# Breakout.net
KiCad netlist of a schematic drawn in EAGLE
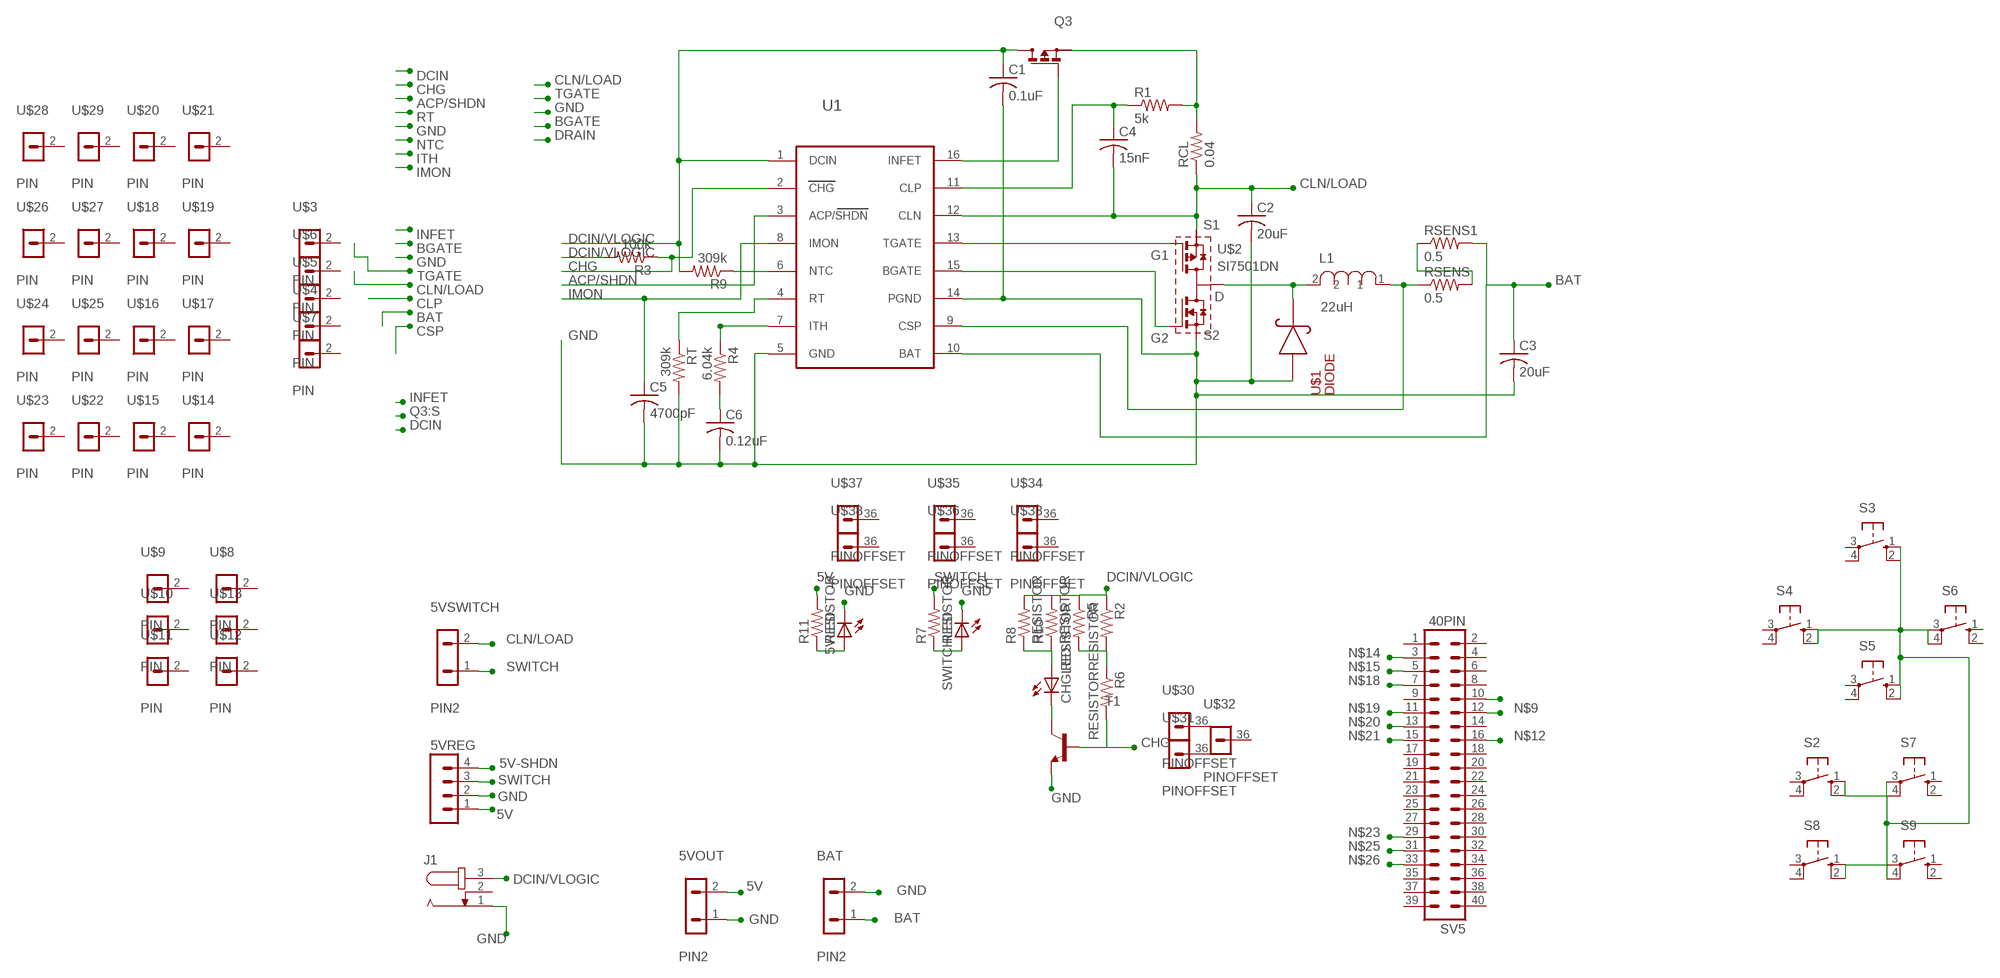
[diagram p0: schematic, sheet 1]

(export (version "E")
  (design (tool "Eeschema 10.0.6"))
  (components
    (comp (ref "5VLED")
      (value "LED5MM")
      (footprint "eagle-import:LED5MM")
      (libsource (lib "eagle-import") (part "LED5MM"))
    )
    (comp (ref "5VOUT")
      (value "PIN2")
      (footprint "eagle-import:PIN2")
      (libsource (lib "eagle-import") (part "PIN2"))
    )
    (comp (ref "5VREG")
      (value "MA04-1")
      (footprint "eagle-import:MA04-1")
      (libsource (lib "eagle-import") (part "MA04-1"))
    )
    (comp (ref "5VSWITCH")
      (value "PIN2")
      (footprint "eagle-import:PIN2")
      (libsource (lib "eagle-import") (part "PIN2"))
    )
    (comp (ref "BAT")
      (value "PIN2")
      (footprint "eagle-import:PIN2")
      (libsource (lib "eagle-import") (part "PIN2"))
    )
    (comp (ref "C1")
      (value "0.1uF")
      (footprint "eagle-import:C1210")
      (libsource (lib "eagle-import") (part "C-USC1210"))
    )
    (comp (ref "C2")
      (value "20uF")
      (footprint "eagle-import:C1210")
      (libsource (lib "eagle-import") (part "C-USC1210"))
    )
    (comp (ref "C3")
      (value "20uF")
      (footprint "eagle-import:C1210")
      (libsource (lib "eagle-import") (part "C-USC1210"))
    )
    (comp (ref "C4")
      (value "15nF")
      (footprint "eagle-import:C1210")
      (libsource (lib "eagle-import") (part "C-USC1210"))
    )
    (comp (ref "C5")
      (value "4700pF")
      (footprint "eagle-import:C1210")
      (libsource (lib "eagle-import") (part "C-USC1210"))
    )
    (comp (ref "C6")
      (value "0.12uF")
      (footprint "eagle-import:C1210")
      (libsource (lib "eagle-import") (part "C-USC1210"))
    )
    (comp (ref "CHGLED")
      (value "LED5MM")
      (footprint "eagle-import:LED5MM")
      (libsource (lib "eagle-import") (part "LED5MM"))
    )
    (comp (ref "J1")
      (value "JACK-PLUG0")
      (footprint "eagle-import:SPC4077")
      (libsource (lib "eagle-import") (part "JACK-PLUG0"))
    )
    (comp (ref "L1")
      (value "22uH")
      (footprint "eagle-import:POWERINDUCTOR")
      (libsource (lib "eagle-import") (part "SDR1005INDUCTOR"))
    )
    (comp (ref "Q3")
      (value "MOSFET")
      (footprint "eagle-import:SOT-23")
      (libsource (lib "eagle-import") (part "MOSFET"))
    )
    (comp (ref "R1")
      (value "5k")
      (footprint "eagle-import:R1206")
      (libsource (lib "eagle-import") (part "R-US_R1206"))
    )
    (comp (ref "R2")
      (value "RESISTOR")
      (footprint "eagle-import:RESISTOR")
      (libsource (lib "eagle-import") (part "RESISTOR"))
    )
    (comp (ref "R3")
      (value "100k")
      (footprint "eagle-import:R1206")
      (libsource (lib "eagle-import") (part "R-US_R1206"))
    )
    (comp (ref "R4")
      (value "6.04k")
      (footprint "eagle-import:R1206")
      (libsource (lib "eagle-import") (part "R-US_R1206"))
    )
    (comp (ref "R5")
      (value "RESISTOR")
      (footprint "eagle-import:RESISTOR")
      (libsource (lib "eagle-import") (part "RESISTOR"))
    )
    (comp (ref "R6")
      (value "RESISTOR")
      (footprint "eagle-import:RESISTOR")
      (libsource (lib "eagle-import") (part "RESISTOR"))
    )
    (comp (ref "R7")
      (value "RESISTOR")
      (footprint "eagle-import:RESISTOR")
      (libsource (lib "eagle-import") (part "RESISTOR"))
    )
    (comp (ref "R8")
      (value "RESISTOR")
      (footprint "eagle-import:RESISTOR")
      (libsource (lib "eagle-import") (part "RESISTOR"))
    )
    (comp (ref "R9")
      (value "309k")
      (footprint "eagle-import:R1206")
      (libsource (lib "eagle-import") (part "R-US_R1206"))
    )
    (comp (ref "R10")
      (value "RESISTOR")
      (footprint "eagle-import:RESISTOR")
      (libsource (lib "eagle-import") (part "RESISTOR"))
    )
    (comp (ref "R11")
      (value "RESISTOR")
      (footprint "eagle-import:RESISTOR")
      (libsource (lib "eagle-import") (part "RESISTOR"))
    )
    (comp (ref "RCL")
      (value "0.04")
      (footprint "eagle-import:R1206")
      (libsource (lib "eagle-import") (part "R-US_R1206"))
    )
    (comp (ref "RSENS")
      (value "0.5")
      (footprint "eagle-import:0612_1632")
      (libsource (lib "eagle-import") (part "0612/1632"))
    )
    (comp (ref "RSENS1")
      (value "0.5")
      (footprint "eagle-import:0612_1632")
      (libsource (lib "eagle-import") (part "0612/1632"))
    )
    (comp (ref "RT")
      (value "309k")
      (footprint "eagle-import:R1206")
      (libsource (lib "eagle-import") (part "R-US_R1206"))
    )
    (comp (ref "S2")
      (value "10-XX")
      (footprint "eagle-import:B3F-10XX")
      (fields (field (name "MPN") "B3F-1000"))
      (libsource (lib "eagle-import") (part "10-XX"))
    )
    (comp (ref "S3")
      (value "10-XX")
      (footprint "eagle-import:B3F-10XX")
      (fields (field (name "MPN") "B3F-1000"))
      (libsource (lib "eagle-import") (part "10-XX"))
    )
    (comp (ref "S4")
      (value "10-XX")
      (footprint "eagle-import:B3F-10XX")
      (fields (field (name "MPN") "B3F-1000"))
      (libsource (lib "eagle-import") (part "10-XX"))
    )
    (comp (ref "S5")
      (value "10-XX")
      (footprint "eagle-import:B3F-10XX")
      (fields (field (name "MPN") "B3F-1000"))
      (libsource (lib "eagle-import") (part "10-XX"))
    )
    (comp (ref "S6")
      (value "10-XX")
      (footprint "eagle-import:B3F-10XX")
      (fields (field (name "MPN") "B3F-1000"))
      (libsource (lib "eagle-import") (part "10-XX"))
    )
    (comp (ref "S7")
      (value "10-XX")
      (footprint "eagle-import:B3F-10XX")
      (fields (field (name "MPN") "B3F-1000"))
      (libsource (lib "eagle-import") (part "10-XX"))
    )
    (comp (ref "S8")
      (value "10-XX")
      (footprint "eagle-import:B3F-10XX")
      (fields (field (name "MPN") "B3F-1000"))
      (libsource (lib "eagle-import") (part "10-XX"))
    )
    (comp (ref "S9")
      (value "10-XX")
      (footprint "eagle-import:B3F-10XX")
      (fields (field (name "MPN") "B3F-1000"))
      (libsource (lib "eagle-import") (part "10-XX"))
    )
    (comp (ref "SV5")
      (value "40PIN")
      (footprint "eagle-import:40PINHEADDER")
      (libsource (lib "eagle-import") (part "40PIN"))
    )
    (comp (ref "SWITCHLED")
      (value "LED5MM")
      (footprint "eagle-import:LED5MM")
      (libsource (lib "eagle-import") (part "LED5MM"))
    )
    (comp (ref "T1")
      (value "-NPN-TO92-E1")
      (footprint "eagle-import:TO92-E1")
      (libsource (lib "eagle-import") (part "-NPN-TO92-E1"))
    )
    (comp (ref "U$1")
      (value "DIODE")
      (footprint "eagle-import:DIODE")
      (libsource (lib "eagle-import") (part "DIODE"))
    )
    (comp (ref "U$2")
      (value "SI7501DN")
      (footprint "eagle-import:POWERPAK")
      (libsource (lib "eagle-import") (part "SI7501DN"))
    )
    (comp (ref "U$3")
      (value "PIN")
      (footprint "eagle-import:PIN")
      (libsource (lib "eagle-import") (part "PIN"))
    )
    (comp (ref "U$4")
      (value "PIN")
      (footprint "eagle-import:PIN")
      (libsource (lib "eagle-import") (part "PIN"))
    )
    (comp (ref "U$5")
      (value "PIN")
      (footprint "eagle-import:PIN")
      (libsource (lib "eagle-import") (part "PIN"))
    )
    (comp (ref "U$6")
      (value "PIN")
      (footprint "eagle-import:PIN")
      (libsource (lib "eagle-import") (part "PIN"))
    )
    (comp (ref "U$7")
      (value "PIN")
      (footprint "eagle-import:PIN")
      (libsource (lib "eagle-import") (part "PIN"))
    )
    (comp (ref "U$8")
      (value "PIN")
      (footprint "eagle-import:PIN")
      (libsource (lib "eagle-import") (part "PIN"))
    )
    (comp (ref "U$9")
      (value "PIN")
      (footprint "eagle-import:PIN")
      (libsource (lib "eagle-import") (part "PIN"))
    )
    (comp (ref "U$10")
      (value "PIN")
      (footprint "eagle-import:PIN")
      (libsource (lib "eagle-import") (part "PIN"))
    )
    (comp (ref "U$11")
      (value "PIN")
      (footprint "eagle-import:PIN")
      (libsource (lib "eagle-import") (part "PIN"))
    )
    (comp (ref "U$12")
      (value "PIN")
      (footprint "eagle-import:PIN")
      (libsource (lib "eagle-import") (part "PIN"))
    )
    (comp (ref "U$13")
      (value "PIN")
      (footprint "eagle-import:PIN")
      (libsource (lib "eagle-import") (part "PIN"))
    )
    (comp (ref "U$14")
      (value "PIN")
      (footprint "eagle-import:PIN")
      (libsource (lib "eagle-import") (part "PIN"))
    )
    (comp (ref "U$15")
      (value "PIN")
      (footprint "eagle-import:PIN")
      (libsource (lib "eagle-import") (part "PIN"))
    )
    (comp (ref "U$16")
      (value "PIN")
      (footprint "eagle-import:PIN")
      (libsource (lib "eagle-import") (part "PIN"))
    )
    (comp (ref "U$17")
      (value "PIN")
      (footprint "eagle-import:PIN")
      (libsource (lib "eagle-import") (part "PIN"))
    )
    (comp (ref "U$18")
      (value "PIN")
      (footprint "eagle-import:PIN")
      (libsource (lib "eagle-import") (part "PIN"))
    )
    (comp (ref "U$19")
      (value "PIN")
      (footprint "eagle-import:PIN")
      (libsource (lib "eagle-import") (part "PIN"))
    )
    (comp (ref "U$20")
      (value "PIN")
      (footprint "eagle-import:PIN")
      (libsource (lib "eagle-import") (part "PIN"))
    )
    (comp (ref "U$21")
      (value "PIN")
      (footprint "eagle-import:PIN")
      (libsource (lib "eagle-import") (part "PIN"))
    )
    (comp (ref "U$22")
      (value "PIN")
      (footprint "eagle-import:PIN")
      (libsource (lib "eagle-import") (part "PIN"))
    )
    (comp (ref "U$23")
      (value "PIN")
      (footprint "eagle-import:PIN")
      (libsource (lib "eagle-import") (part "PIN"))
    )
    (comp (ref "U$24")
      (value "PIN")
      (footprint "eagle-import:PIN")
      (libsource (lib "eagle-import") (part "PIN"))
    )
    (comp (ref "U$25")
      (value "PIN")
      (footprint "eagle-import:PIN")
      (libsource (lib "eagle-import") (part "PIN"))
    )
    (comp (ref "U$26")
      (value "PIN")
      (footprint "eagle-import:PIN")
      (libsource (lib "eagle-import") (part "PIN"))
    )
    (comp (ref "U$27")
      (value "PIN")
      (footprint "eagle-import:PIN")
      (libsource (lib "eagle-import") (part "PIN"))
    )
    (comp (ref "U$28")
      (value "PIN")
      (footprint "eagle-import:PIN")
      (libsource (lib "eagle-import") (part "PIN"))
    )
    (comp (ref "U$29")
      (value "PIN")
      (footprint "eagle-import:PIN")
      (libsource (lib "eagle-import") (part "PIN"))
    )
    (comp (ref "U$30")
      (value "PINOFFSET")
      (footprint "eagle-import:PINOFFST")
      (libsource (lib "eagle-import") (part "PINOFFSET"))
    )
    (comp (ref "U$31")
      (value "PINOFFSET")
      (footprint "eagle-import:PINOFFST")
      (libsource (lib "eagle-import") (part "PINOFFSET"))
    )
    (comp (ref "U$32")
      (value "PINOFFSET")
      (footprint "eagle-import:PINOFFST")
      (libsource (lib "eagle-import") (part "PINOFFSET"))
    )
    (comp (ref "U$33")
      (value "PINOFFSET")
      (footprint "eagle-import:PINOFFST")
      (libsource (lib "eagle-import") (part "PINOFFSET"))
    )
    (comp (ref "U$34")
      (value "PINOFFSET")
      (footprint "eagle-import:PINOFFST")
      (libsource (lib "eagle-import") (part "PINOFFSET"))
    )
    (comp (ref "U$35")
      (value "PINOFFSET")
      (footprint "eagle-import:PINOFFST")
      (libsource (lib "eagle-import") (part "PINOFFSET"))
    )
    (comp (ref "U$36")
      (value "PINOFFSET")
      (footprint "eagle-import:PINOFFST")
      (libsource (lib "eagle-import") (part "PINOFFSET"))
    )
    (comp (ref "U$37")
      (value "PINOFFSET")
      (footprint "eagle-import:PINOFFST")
      (libsource (lib "eagle-import") (part "PINOFFSET"))
    )
    (comp (ref "U$38")
      (value "PINOFFSET")
      (footprint "eagle-import:PINOFFST")
      (libsource (lib "eagle-import") (part "PINOFFSET"))
    )
    (comp (ref "U1")
      (value "LTC6004")
      (footprint "eagle-import:SSOP-16")
      (libsource (lib "eagle-import") (part "LTC6004"))
    )
  )
  (nets
    (net (code "1") (name "/5V") (class "Default")
      (node (ref "5VOUT") (pin "2") (pinfunction "2_2") (pintype "passive"))
      (node (ref "5VREG") (pin "1") (pinfunction "1_1") (pintype "passive"))
      (node (ref "R11") (pin "1") (pinfunction "2_1") (pintype "passive"))
    )
    (net (code "2") (name "/5V-SHDN") (class "Default")
      (node (ref "5VREG") (pin "4") (pinfunction "4_4") (pintype "passive"))
    )
    (net (code "3") (name "/ACP{slash}SHDN") (class "Default")
      (node (ref "U1") (pin "3") (pinfunction "ACP/SHDN_3") (pintype "power_in"))
    )
    (net (code "4") (name "/BAT") (class "Default")
      (node (ref "BAT") (pin "1") (pinfunction "1_1") (pintype "passive"))
      (node (ref "C3") (pin "1") (pinfunction "1_1") (pintype "passive"))
      (node (ref "RSENS1") (pin "2") (pinfunction "2_2") (pintype "passive"))
      (node (ref "U1") (pin "10") (pinfunction "BAT_10") (pintype "power_in"))
    )
    (net (code "5") (name "/BGATE") (class "Default")
      (node (ref "U$2") (pin "G2") (pinfunction "G2_G2") (pintype "passive"))
      (node (ref "U1") (pin "15") (pinfunction "BGATE_15") (pintype "power_in"))
    )
    (net (code "6") (name "/CHG") (class "Default")
      (node (ref "R3") (pin "1") (pinfunction "1_1") (pintype "passive"))
      (node (ref "R6") (pin "1") (pinfunction "2_1") (pintype "passive"))
      (node (ref "T1") (pin "2") (pinfunction "B_2") (pintype "passive"))
      (node (ref "U1") (pin "2") (pinfunction "CHG_2") (pintype "power_in"))
    )
    (net (code "7") (name "/CLN{slash}LOAD") (class "Default")
      (node (ref "5VSWITCH") (pin "2") (pinfunction "2_2") (pintype "passive"))
      (node (ref "C2") (pin "1") (pinfunction "1_1") (pintype "passive"))
      (node (ref "C4") (pin "2") (pinfunction "2_2") (pintype "passive"))
      (node (ref "RCL") (pin "1") (pinfunction "1_1") (pintype "passive"))
      (node (ref "U$2") (pin "S1") (pinfunction "S1_S1") (pintype "passive"))
      (node (ref "U1") (pin "12") (pinfunction "CLN_12") (pintype "power_in"))
    )
    (net (code "8") (name "/CLP") (class "Default")
      (node (ref "C4") (pin "1") (pinfunction "1_1") (pintype "passive"))
      (node (ref "R1") (pin "1") (pinfunction "1_1") (pintype "passive"))
      (node (ref "U1") (pin "11") (pinfunction "CLP_11") (pintype "output"))
    )
    (net (code "9") (name "/CSP") (class "Default")
      (node (ref "L1") (pin "1") (pinfunction "1_1") (pintype "passive"))
      (node (ref "RSENS") (pin "1") (pinfunction "1_1") (pintype "passive"))
      (node (ref "U1") (pin "9") (pinfunction "CSP_9") (pintype "power_in"))
    )
    (net (code "11") (name "/DCIN{slash}VLOGIC") (class "Default")
      (node (ref "C1") (pin "1") (pinfunction "1_1") (pintype "passive"))
      (node (ref "J1") (pin "3") (pinfunction "3_3") (pintype "passive"))
      (node (ref "Q3") (pin "DRAIN") (pinfunction "D_DRAIN") (pintype "passive"))
      (node (ref "R10") (pin "1") (pinfunction "2_1") (pintype "passive"))
      (node (ref "R2") (pin "2") (pinfunction "1_2") (pintype "passive"))
      (node (ref "R3") (pin "2") (pinfunction "2_2") (pintype "passive"))
      (node (ref "R5") (pin "2") (pinfunction "1_2") (pintype "passive"))
      (node (ref "R8") (pin "1") (pinfunction "2_1") (pintype "passive"))
      (node (ref "R9") (pin "2") (pinfunction "2_2") (pintype "passive"))
      (node (ref "U1") (pin "1") (pinfunction "DCIN_1") (pintype "power_in"))
    )
    (net (code "12") (name "/DRAIN") (class "Default")
      (node (ref "L1") (pin "2") (pinfunction "2_2") (pintype "passive"))
      (node (ref "U$1") (pin "P$1") (pinfunction "2_P$1") (pintype "bidirectional"))
      (node (ref "U$2") (pin "D") (pinfunction "D_D") (pintype "passive"))
    )
    (net (code "13") (name "/GND") (class "Default")
      (node (ref "5VLED") (pin "K") (pinfunction "C_K") (pintype "passive"))
      (node (ref "5VOUT") (pin "1") (pinfunction "1_1") (pintype "passive"))
      (node (ref "5VREG") (pin "2") (pinfunction "2_2") (pintype "passive"))
      (node (ref "BAT") (pin "2") (pinfunction "2_2") (pintype "passive"))
      (node (ref "C1") (pin "2") (pinfunction "2_2") (pintype "passive"))
      (node (ref "C2") (pin "2") (pinfunction "2_2") (pintype "passive"))
      (node (ref "C3") (pin "2") (pinfunction "2_2") (pintype "passive"))
      (node (ref "C5") (pin "2") (pinfunction "2_2") (pintype "passive"))
      (node (ref "C6") (pin "2") (pinfunction "2_2") (pintype "passive"))
      (node (ref "J1") (pin "1") (pinfunction "1_1") (pintype "passive"))
      (node (ref "RT") (pin "2") (pinfunction "2_2") (pintype "passive"))
      (node (ref "S2") (pin "1") (pinfunction "S_1") (pintype "passive"))
      (node (ref "S2") (pin "2") (pinfunction "S1_2") (pintype "passive"))
      (node (ref "S3") (pin "1") (pinfunction "S_1") (pintype "passive"))
      (node (ref "S3") (pin "2") (pinfunction "S1_2") (pintype "passive"))
      (node (ref "S4") (pin "1") (pinfunction "S_1") (pintype "passive"))
      (node (ref "S4") (pin "2") (pinfunction "S1_2") (pintype "passive"))
      (node (ref "S5") (pin "1") (pinfunction "S_1") (pintype "passive"))
      (node (ref "S5") (pin "2") (pinfunction "S1_2") (pintype "passive"))
      (node (ref "S6") (pin "3") (pinfunction "P_3") (pintype "passive"))
      (node (ref "S6") (pin "4") (pinfunction "P1_4") (pintype "passive"))
      (node (ref "S7") (pin "3") (pinfunction "P_3") (pintype "passive"))
      (node (ref "S7") (pin "4") (pinfunction "P1_4") (pintype "passive"))
      (node (ref "S8") (pin "1") (pinfunction "S_1") (pintype "passive"))
      (node (ref "S8") (pin "2") (pinfunction "S1_2") (pintype "passive"))
      (node (ref "S9") (pin "3") (pinfunction "P_3") (pintype "passive"))
      (node (ref "S9") (pin "4") (pinfunction "P1_4") (pintype "passive"))
      (node (ref "SWITCHLED") (pin "K") (pinfunction "C_K") (pintype "passive"))
      (node (ref "T1") (pin "3") (pinfunction "E_3") (pintype "passive"))
      (node (ref "U$1") (pin "P$2") (pinfunction "1_P$2") (pintype "bidirectional"))
      (node (ref "U$2") (pin "S2") (pinfunction "S2_S2") (pintype "passive"))
      (node (ref "U1") (pin "14") (pinfunction "PGND_14") (pintype "power_in"))
      (node (ref "U1") (pin "5") (pinfunction "GND_5") (pintype "input"))
    )
    (net (code "14") (name "/IMON") (class "Default")
      (node (ref "C5") (pin "1") (pinfunction "1_1") (pintype "passive"))
      (node (ref "U1") (pin "8") (pinfunction "IMON_8") (pintype "power_in"))
    )
    (net (code "15") (name "/INFET") (class "Default")
      (node (ref "Q3") (pin "GATE") (pinfunction "G_GATE") (pintype "passive"))
      (node (ref "U1") (pin "16") (pinfunction "INFET_16") (pintype "output"))
    )
    (net (code "16") (name "/ITH") (class "Default")
      (node (ref "R4") (pin "1") (pinfunction "1_1") (pintype "passive"))
      (node (ref "U1") (pin "7") (pinfunction "ITH_7") (pintype "input"))
    )
    (net (code "17") (name "/N$9") (class "Default")
      (node (ref "SV5") (pin "12") (pinfunction "12_12") (pintype "passive"))
    )
    (net (code "18") (name "/N$12") (class "Default")
      (node (ref "SV5") (pin "16") (pinfunction "16_16") (pintype "passive"))
    )
    (net (code "19") (name "/N$14") (class "Default")
      (node (ref "SV5") (pin "3") (pinfunction "3_3") (pintype "passive"))
    )
    (net (code "20") (name "/N$15") (class "Default")
      (node (ref "SV5") (pin "5") (pinfunction "5_5") (pintype "passive"))
    )
    (net (code "21") (name "/N$18") (class "Default")
      (node (ref "SV5") (pin "7") (pinfunction "7_7") (pintype "passive"))
    )
    (net (code "22") (name "/N$19") (class "Default")
      (node (ref "SV5") (pin "11") (pinfunction "11_11") (pintype "passive"))
    )
    (net (code "23") (name "/N$20") (class "Default")
      (node (ref "SV5") (pin "13") (pinfunction "13_13") (pintype "passive"))
    )
    (net (code "24") (name "/N$21") (class "Default")
      (node (ref "SV5") (pin "15") (pinfunction "15_15") (pintype "passive"))
    )
    (net (code "25") (name "/N$23") (class "Default")
      (node (ref "SV5") (pin "29") (pinfunction "29_29") (pintype "passive"))
    )
    (net (code "26") (name "/N$25") (class "Default")
      (node (ref "SV5") (pin "31") (pinfunction "31_31") (pintype "passive"))
    )
    (net (code "27") (name "/N$26") (class "Default")
      (node (ref "SV5") (pin "33") (pinfunction "33_33") (pintype "passive"))
    )
    (net (code "28") (name "/NTC") (class "Default")
      (node (ref "R9") (pin "1") (pinfunction "1_1") (pintype "passive"))
      (node (ref "U1") (pin "6") (pinfunction "NTC_6") (pintype "power_in"))
    )
    (net (code "29") (name "/Q3:S") (class "Default")
      (node (ref "Q3") (pin "SOURCE") (pinfunction "S_SOURCE") (pintype "passive"))
      (node (ref "R1") (pin "2") (pinfunction "2_2") (pintype "passive"))
      (node (ref "RCL") (pin "2") (pinfunction "2_2") (pintype "passive"))
    )
    (net (code "30") (name "/RT") (class "Default")
      (node (ref "RT") (pin "1") (pinfunction "1_1") (pintype "passive"))
      (node (ref "U1") (pin "4") (pinfunction "RT_4") (pintype "input"))
    )
    (net (code "31") (name "/SWITCH") (class "Default")
      (node (ref "5VREG") (pin "3") (pinfunction "3_3") (pintype "passive"))
      (node (ref "5VSWITCH") (pin "1") (pinfunction "1_1") (pintype "passive"))
      (node (ref "R7") (pin "1") (pinfunction "2_1") (pintype "passive"))
    )
    (net (code "32") (name "/TGATE") (class "Default")
      (node (ref "U$2") (pin "G1") (pinfunction "G1_G1") (pintype "passive"))
      (node (ref "U1") (pin "13") (pinfunction "TGATE_13") (pintype "input"))
    )
    (net (code "33") (name "Net-(C6-Pad1)") (class "Default")
      (node (ref "C6") (pin "1") (pinfunction "1_1") (pintype "passive"))
      (node (ref "R4") (pin "2") (pinfunction "2_2") (pintype "passive"))
    )
    (net (code "34") (name "Net-(CHGLED-C)") (class "Default")
      (node (ref "CHGLED") (pin "K") (pinfunction "C_K") (pintype "passive"))
      (node (ref "T1") (pin "1") (pinfunction "C_1") (pintype "passive"))
    )
    (net (code "35") (name "Net-(R2-2)") (class "Default")
      (node (ref "R2") (pin "1") (pinfunction "2_1") (pintype "passive"))
      (node (ref "R5") (pin "1") (pinfunction "2_1") (pintype "passive"))
      (node (ref "R6") (pin "2") (pinfunction "1_2") (pintype "passive"))
    )
    (net (code "36") (name "Net-(R7-1)") (class "Default")
      (node (ref "R7") (pin "2") (pinfunction "1_2") (pintype "passive"))
      (node (ref "SWITCHLED") (pin "A") (pinfunction "A_A") (pintype "passive"))
    )
    (net (code "37") (name "Net-(R10-1)") (class "Default")
      (node (ref "CHGLED") (pin "A") (pinfunction "A_A") (pintype "passive"))
      (node (ref "R10") (pin "2") (pinfunction "1_2") (pintype "passive"))
      (node (ref "R8") (pin "2") (pinfunction "1_2") (pintype "passive"))
    )
    (net (code "38") (name "Net-(R11-1)") (class "Default")
      (node (ref "5VLED") (pin "A") (pinfunction "A_A") (pintype "passive"))
      (node (ref "R11") (pin "2") (pinfunction "1_2") (pintype "passive"))
    )
    (net (code "39") (name "Net-(RSENS-Pad2)") (class "Default")
      (node (ref "RSENS") (pin "2") (pinfunction "2_2") (pintype "passive"))
      (node (ref "RSENS1") (pin "1") (pinfunction "1_1") (pintype "passive"))
    )
    (net (code "40") (name "unconnected-(J1-Pad2)") (class "Default")
      (node (ref "J1") (pin "2") (pinfunction "2_2") (pintype "passive"))
    )
    (net (code "41") (name "unconnected-(S2-P-Pad3)") (class "Default")
      (node (ref "S2") (pin "3") (pinfunction "P_3") (pintype "passive"))
    )
    (net (code "42") (name "unconnected-(S2-P1-Pad4)") (class "Default")
      (node (ref "S2") (pin "4") (pinfunction "P1_4") (pintype "passive"))
    )
    (net (code "43") (name "unconnected-(S3-P-Pad3)") (class "Default")
      (node (ref "S3") (pin "3") (pinfunction "P_3") (pintype "passive"))
    )
    (net (code "44") (name "unconnected-(S3-P1-Pad4)") (class "Default")
      (node (ref "S3") (pin "4") (pinfunction "P1_4") (pintype "passive"))
    )
    (net (code "45") (name "unconnected-(S4-P-Pad3)") (class "Default")
      (node (ref "S4") (pin "3") (pinfunction "P_3") (pintype "passive"))
    )
    (net (code "46") (name "unconnected-(S4-P1-Pad4)") (class "Default")
      (node (ref "S4") (pin "4") (pinfunction "P1_4") (pintype "passive"))
    )
    (net (code "47") (name "unconnected-(S5-P-Pad3)") (class "Default")
      (node (ref "S5") (pin "3") (pinfunction "P_3") (pintype "passive"))
    )
    (net (code "48") (name "unconnected-(S5-P1-Pad4)") (class "Default")
      (node (ref "S5") (pin "4") (pinfunction "P1_4") (pintype "passive"))
    )
    (net (code "49") (name "unconnected-(S6-S-Pad1)") (class "Default")
      (node (ref "S6") (pin "1") (pinfunction "S_1") (pintype "passive"))
    )
    (net (code "50") (name "unconnected-(S6-S1-Pad2)") (class "Default")
      (node (ref "S6") (pin "2") (pinfunction "S1_2") (pintype "passive"))
    )
    (net (code "51") (name "unconnected-(S7-S-Pad1)") (class "Default")
      (node (ref "S7") (pin "1") (pinfunction "S_1") (pintype "passive"))
    )
    (net (code "52") (name "unconnected-(S7-S1-Pad2)") (class "Default")
      (node (ref "S7") (pin "2") (pinfunction "S1_2") (pintype "passive"))
    )
    (net (code "53") (name "unconnected-(S8-P-Pad3)") (class "Default")
      (node (ref "S8") (pin "3") (pinfunction "P_3") (pintype "passive"))
    )
    (net (code "54") (name "unconnected-(S8-P1-Pad4)") (class "Default")
      (node (ref "S8") (pin "4") (pinfunction "P1_4") (pintype "passive"))
    )
    (net (code "55") (name "unconnected-(S9-S-Pad1)") (class "Default")
      (node (ref "S9") (pin "1") (pinfunction "S_1") (pintype "passive"))
    )
    (net (code "56") (name "unconnected-(S9-S1-Pad2)") (class "Default")
      (node (ref "S9") (pin "2") (pinfunction "S1_2") (pintype "passive"))
    )
    (net (code "57") (name "unconnected-(SV5-Pad1)") (class "Default")
      (node (ref "SV5") (pin "1") (pinfunction "1_1") (pintype "passive"))
    )
    (net (code "58") (name "unconnected-(SV5-Pad2)") (class "Default")
      (node (ref "SV5") (pin "2") (pinfunction "2_2") (pintype "passive"))
    )
    (net (code "59") (name "unconnected-(SV5-Pad4)") (class "Default")
      (node (ref "SV5") (pin "4") (pinfunction "4_4") (pintype "passive"))
    )
    (net (code "60") (name "unconnected-(SV5-Pad6)") (class "Default")
      (node (ref "SV5") (pin "6") (pinfunction "6_6") (pintype "passive"))
    )
    (net (code "61") (name "unconnected-(SV5-Pad8)") (class "Default")
      (node (ref "SV5") (pin "8") (pinfunction "8_8") (pintype "passive"))
    )
    (net (code "62") (name "unconnected-(SV5-Pad9)") (class "Default")
      (node (ref "SV5") (pin "9") (pinfunction "9_9") (pintype "passive"))
    )
    (net (code "63") (name "unconnected-(SV5-Pad10)") (class "Default")
      (node (ref "SV5") (pin "10") (pinfunction "10_10") (pintype "passive"))
    )
    (net (code "64") (name "unconnected-(SV5-Pad14)") (class "Default")
      (node (ref "SV5") (pin "14") (pinfunction "14_14") (pintype "passive"))
    )
    (net (code "65") (name "unconnected-(SV5-Pad17)") (class "Default")
      (node (ref "SV5") (pin "17") (pinfunction "17_17") (pintype "passive"))
    )
    (net (code "66") (name "unconnected-(SV5-Pad18)") (class "Default")
      (node (ref "SV5") (pin "18") (pinfunction "18_18") (pintype "passive"))
    )
    (net (code "67") (name "unconnected-(SV5-Pad19)") (class "Default")
      (node (ref "SV5") (pin "19") (pinfunction "19_19") (pintype "passive"))
    )
    (net (code "68") (name "unconnected-(SV5-Pad20)") (class "Default")
      (node (ref "SV5") (pin "20") (pinfunction "20_20") (pintype "passive"))
    )
    (net (code "69") (name "unconnected-(SV5-Pad21)") (class "Default")
      (node (ref "SV5") (pin "21") (pinfunction "21_21") (pintype "passive"))
    )
    (net (code "70") (name "unconnected-(SV5-Pad22)") (class "Default")
      (node (ref "SV5") (pin "22") (pinfunction "22_22") (pintype "passive"))
    )
    (net (code "71") (name "unconnected-(SV5-Pad23)") (class "Default")
      (node (ref "SV5") (pin "23") (pinfunction "23_23") (pintype "passive"))
    )
    (net (code "72") (name "unconnected-(SV5-Pad24)") (class "Default")
      (node (ref "SV5") (pin "24") (pinfunction "24_24") (pintype "passive"))
    )
    (net (code "73") (name "unconnected-(SV5-Pad25)") (class "Default")
      (node (ref "SV5") (pin "25") (pinfunction "25_25") (pintype "passive"))
    )
    (net (code "74") (name "unconnected-(SV5-Pad26)") (class "Default")
      (node (ref "SV5") (pin "26") (pinfunction "26_26") (pintype "passive"))
    )
    (net (code "75") (name "unconnected-(SV5-Pad27)") (class "Default")
      (node (ref "SV5") (pin "27") (pinfunction "27_27") (pintype "passive"))
    )
    (net (code "76") (name "unconnected-(SV5-Pad28)") (class "Default")
      (node (ref "SV5") (pin "28") (pinfunction "28_28") (pintype "passive"))
    )
    (net (code "77") (name "unconnected-(SV5-Pad30)") (class "Default")
      (node (ref "SV5") (pin "30") (pinfunction "30_30") (pintype "passive"))
    )
    (net (code "78") (name "unconnected-(SV5-Pad32)") (class "Default")
      (node (ref "SV5") (pin "32") (pinfunction "32_32") (pintype "passive"))
    )
    (net (code "79") (name "unconnected-(SV5-Pad34)") (class "Default")
      (node (ref "SV5") (pin "34") (pinfunction "34_34") (pintype "passive"))
    )
    (net (code "80") (name "unconnected-(SV5-Pad35)") (class "Default")
      (node (ref "SV5") (pin "35") (pinfunction "35_35") (pintype "passive"))
    )
    (net (code "81") (name "unconnected-(SV5-Pad36)") (class "Default")
      (node (ref "SV5") (pin "36") (pinfunction "36_36") (pintype "passive"))
    )
    (net (code "82") (name "unconnected-(SV5-Pad37)") (class "Default")
      (node (ref "SV5") (pin "37") (pinfunction "37_37") (pintype "passive"))
    )
    (net (code "83") (name "unconnected-(SV5-Pad38)") (class "Default")
      (node (ref "SV5") (pin "38") (pinfunction "38_38") (pintype "passive"))
    )
    (net (code "84") (name "unconnected-(SV5-Pad39)") (class "Default")
      (node (ref "SV5") (pin "39") (pinfunction "39_39") (pintype "passive"))
    )
    (net (code "85") (name "unconnected-(SV5-Pad40)") (class "Default")
      (node (ref "SV5") (pin "40") (pinfunction "40_40") (pintype "passive"))
    )
    (net (code "86") (name "unconnected-(U$3-Pad2)") (class "Default")
      (node (ref "U$3") (pin "2") (pinfunction "2_2") (pintype "passive"))
    )
    (net (code "87") (name "unconnected-(U$4-Pad2)") (class "Default")
      (node (ref "U$4") (pin "2") (pinfunction "2_2") (pintype "passive"))
    )
    (net (code "88") (name "unconnected-(U$5-Pad2)") (class "Default")
      (node (ref "U$5") (pin "2") (pinfunction "2_2") (pintype "passive"))
    )
    (net (code "89") (name "unconnected-(U$6-Pad2)") (class "Default")
      (node (ref "U$6") (pin "2") (pinfunction "2_2") (pintype "passive"))
    )
    (net (code "90") (name "unconnected-(U$7-Pad2)") (class "Default")
      (node (ref "U$7") (pin "2") (pinfunction "2_2") (pintype "passive"))
    )
    (net (code "91") (name "unconnected-(U$8-Pad2)") (class "Default")
      (node (ref "U$8") (pin "2") (pinfunction "2_2") (pintype "passive"))
    )
    (net (code "92") (name "unconnected-(U$9-Pad2)") (class "Default")
      (node (ref "U$9") (pin "2") (pinfunction "2_2") (pintype "passive"))
    )
    (net (code "93") (name "unconnected-(U$10-Pad2)") (class "Default")
      (node (ref "U$10") (pin "2") (pinfunction "2_2") (pintype "passive"))
    )
    (net (code "94") (name "unconnected-(U$11-Pad2)") (class "Default")
      (node (ref "U$11") (pin "2") (pinfunction "2_2") (pintype "passive"))
    )
    (net (code "95") (name "unconnected-(U$12-Pad2)") (class "Default")
      (node (ref "U$12") (pin "2") (pinfunction "2_2") (pintype "passive"))
    )
    (net (code "96") (name "unconnected-(U$13-Pad2)") (class "Default")
      (node (ref "U$13") (pin "2") (pinfunction "2_2") (pintype "passive"))
    )
    (net (code "97") (name "unconnected-(U$14-Pad2)") (class "Default")
      (node (ref "U$14") (pin "2") (pinfunction "2_2") (pintype "passive"))
    )
    (net (code "98") (name "unconnected-(U$15-Pad2)") (class "Default")
      (node (ref "U$15") (pin "2") (pinfunction "2_2") (pintype "passive"))
    )
    (net (code "99") (name "unconnected-(U$16-Pad2)") (class "Default")
      (node (ref "U$16") (pin "2") (pinfunction "2_2") (pintype "passive"))
    )
    (net (code "100") (name "unconnected-(U$17-Pad2)") (class "Default")
      (node (ref "U$17") (pin "2") (pinfunction "2_2") (pintype "passive"))
    )
    (net (code "101") (name "unconnected-(U$18-Pad2)") (class "Default")
      (node (ref "U$18") (pin "2") (pinfunction "2_2") (pintype "passive"))
    )
    (net (code "102") (name "unconnected-(U$19-Pad2)") (class "Default")
      (node (ref "U$19") (pin "2") (pinfunction "2_2") (pintype "passive"))
    )
    (net (code "103") (name "unconnected-(U$20-Pad2)") (class "Default")
      (node (ref "U$20") (pin "2") (pinfunction "2_2") (pintype "passive"))
    )
    (net (code "104") (name "unconnected-(U$21-Pad2)") (class "Default")
      (node (ref "U$21") (pin "2") (pinfunction "2_2") (pintype "passive"))
    )
    (net (code "105") (name "unconnected-(U$22-Pad2)") (class "Default")
      (node (ref "U$22") (pin "2") (pinfunction "2_2") (pintype "passive"))
    )
    (net (code "106") (name "unconnected-(U$23-Pad2)") (class "Default")
      (node (ref "U$23") (pin "2") (pinfunction "2_2") (pintype "passive"))
    )
    (net (code "107") (name "unconnected-(U$24-Pad2)") (class "Default")
      (node (ref "U$24") (pin "2") (pinfunction "2_2") (pintype "passive"))
    )
    (net (code "108") (name "unconnected-(U$25-Pad2)") (class "Default")
      (node (ref "U$25") (pin "2") (pinfunction "2_2") (pintype "passive"))
    )
    (net (code "109") (name "unconnected-(U$26-Pad2)") (class "Default")
      (node (ref "U$26") (pin "2") (pinfunction "2_2") (pintype "passive"))
    )
    (net (code "110") (name "unconnected-(U$27-Pad2)") (class "Default")
      (node (ref "U$27") (pin "2") (pinfunction "2_2") (pintype "passive"))
    )
    (net (code "111") (name "unconnected-(U$28-Pad2)") (class "Default")
      (node (ref "U$28") (pin "2") (pinfunction "2_2") (pintype "passive"))
    )
    (net (code "112") (name "unconnected-(U$29-Pad2)") (class "Default")
      (node (ref "U$29") (pin "2") (pinfunction "2_2") (pintype "passive"))
    )
    (net (code "113") (name "unconnected-(U$30-2-Pad36)") (class "Default")
      (node (ref "U$30") (pin "36") (pinfunction "2_36") (pintype "passive"))
    )
    (net (code "114") (name "unconnected-(U$31-2-Pad36)") (class "Default")
      (node (ref "U$31") (pin "36") (pinfunction "2_36") (pintype "passive"))
    )
    (net (code "115") (name "unconnected-(U$32-2-Pad36)") (class "Default")
      (node (ref "U$32") (pin "36") (pinfunction "2_36") (pintype "passive"))
    )
    (net (code "116") (name "unconnected-(U$33-2-Pad36)") (class "Default")
      (node (ref "U$33") (pin "36") (pinfunction "2_36") (pintype "passive"))
    )
    (net (code "117") (name "unconnected-(U$34-2-Pad36)") (class "Default")
      (node (ref "U$34") (pin "36") (pinfunction "2_36") (pintype "passive"))
    )
    (net (code "118") (name "unconnected-(U$35-2-Pad36)") (class "Default")
      (node (ref "U$35") (pin "36") (pinfunction "2_36") (pintype "passive"))
    )
    (net (code "119") (name "unconnected-(U$36-2-Pad36)") (class "Default")
      (node (ref "U$36") (pin "36") (pinfunction "2_36") (pintype "passive"))
    )
    (net (code "120") (name "unconnected-(U$37-2-Pad36)") (class "Default")
      (node (ref "U$37") (pin "36") (pinfunction "2_36") (pintype "passive"))
    )
    (net (code "121") (name "unconnected-(U$38-2-Pad36)") (class "Default")
      (node (ref "U$38") (pin "36") (pinfunction "2_36") (pintype "passive"))
    )
  )
)
